# IRTxRx.net
KiCad netlist of a schematic drawn in Altium Designer
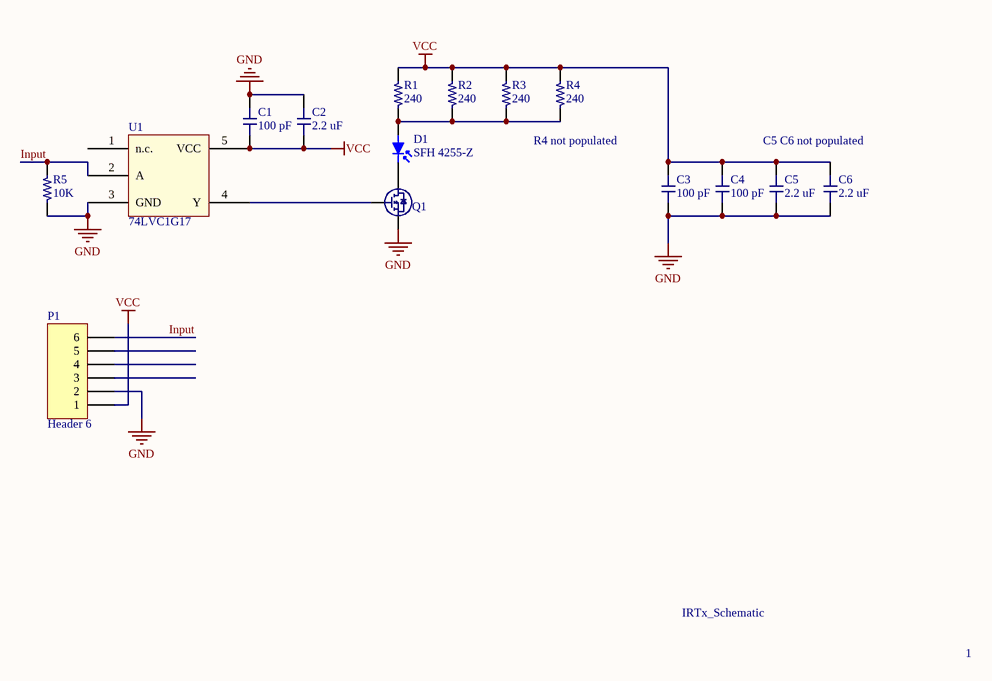
[diagram p0: IRTxRx.SchDoc]

(export (version "E")
  (design (tool "Eeschema 10.0.6"))
  (components
    (comp (ref "C1")
      (value "100 pF")
      (footprint "C_0603")
      (description "CAP CER 100PF 50V C0G/NP0 0603")
      (fields (field (name "Comment") "06035A101JAT2A"))
      (libsource (lib "Capacitor") (part "06035A101JAT2A"))
    )
    (comp (ref "C2")
      (value "2.2 uF")
      (footprint "C_0603")
      (description "Vishay VJ Series")
      (fields (field (name "Comment") "C1608X7R1A225K080AC"))
      (libsource (lib "Capacitor") (part "CAP CER 2.2UF 10V 10% X7R 0603"))
    )
    (comp (ref "C3")
      (value "100 pF")
      (footprint "C_0603")
      (description "CAP CER 100PF 50V C0G/NP0 0603")
      (fields (field (name "Comment") "06035A101JAT2A"))
      (libsource (lib "Capacitor") (part "06035A101JAT2A"))
    )
    (comp (ref "C4")
      (value "100 pF")
      (footprint "C_0603")
      (description "CAP CER 100PF 50V C0G/NP0 0603")
      (fields (field (name "Comment") "06035A101JAT2A"))
      (libsource (lib "Capacitor") (part "06035A101JAT2A"))
    )
    (comp (ref "C5")
      (value "2.2 uF")
      (footprint "C_0603")
      (description "Vishay VJ Series")
      (fields (field (name "Comment") "C1608X7R1A225K080AC"))
      (libsource (lib "Capacitor") (part "CAP CER 2.2UF 10V 10% X7R 0603"))
    )
    (comp (ref "C6")
      (value "2.2 uF")
      (footprint "C_0603")
      (description "Vishay VJ Series")
      (fields (field (name "Comment") "C1608X7R1A225K080AC"))
      (libsource (lib "Capacitor") (part "CAP CER 2.2UF 10V 10% X7R 0603"))
    )
    (comp (ref "D1")
      (value "SFH 4255-Z")
      (footprint "SFH4255")
      (description "EMITTER IR 860NM 100MA SMD")
      (libsource (lib "Diode") (part "SFH 4255-Z"))
    )
    (comp (ref "P1")
      (value "Header 6")
      (footprint "HDR1X6")
      (description "Header, 6-Pin")
      (fields (field (name "PUBLISHER") "Altium Limited"))
      (libsource (lib "Miscellaneous Connectors") (part "Header 6"))
    )
    (comp (ref "Q1")
      (value "ZXMN2A01FTA")
      (footprint "SOT23")
      (description "MOSFET N-CH 20V 1.9A SOT23-3")
      (libsource (lib "Discrete") (part "ZXMN2A01FTA"))
    )
    (comp (ref "R1")
      (value "240")
      (footprint "R_0603")
      (description "Panasonic ERJ-3EK")
      (fields (field (name "Comment") "RES 240 OHM 1/10W 1% 0603 SMD"))
      (libsource (lib "Resistor") (part "RES 240 OHM 1/10W 1% 0603 SMD"))
    )
    (comp (ref "R2")
      (value "240")
      (footprint "R_0603")
      (description "Panasonic ERJ-3EK")
      (fields (field (name "Comment") "RES 240 OHM 1/10W 1% 0603 SMD"))
      (libsource (lib "Resistor") (part "RES 240 OHM 1/10W 1% 0603 SMD"))
    )
    (comp (ref "R3")
      (value "240")
      (footprint "R_0603")
      (description "Panasonic ERJ-3EK")
      (fields (field (name "Comment") "RES 240 OHM 1/10W 1% 0603 SMD"))
      (libsource (lib "Resistor") (part "RES 240 OHM 1/10W 1% 0603 SMD"))
    )
    (comp (ref "R4")
      (value "240")
      (footprint "R_0603")
      (description "Panasonic ERJ-3EK")
      (fields (field (name "Comment") "RES 240 OHM 1/10W 1% 0603 SMD"))
      (libsource (lib "Resistor") (part "RES 240 OHM 1/10W 1% 0603 SMD"))
    )
    (comp (ref "R5")
      (value "10K")
      (footprint "R_0603")
      (description "Panasonic ERJ-3EK")
      (fields (field (name "Comment") "RES 10K OHM 1/10W 1% 0603 SMD"))
      (libsource (lib "Resistor") (part "RES 10K OHM 1/10W 1% 0603 SMD"))
    )
    (comp (ref "U1")
      (value "74LVC1G17")
      (footprint "SOT_353")
      (description "IC BUF NON-INVERT 5.5V 5TSSOP")
      (libsource (lib "Discrete") (part "74LVC1G17"))
    )
  )
  (nets
    (net (code "1") (name "/Input") (class "Default")
      (node (ref "P1") (pin "6") (pinfunction "6_6") (pintype "passive"))
      (node (ref "R5") (pin "1") (pinfunction "1_1") (pintype "passive"))
      (node (ref "U1") (pin "2") (pinfunction "A_2") (pintype "passive"))
    )
    (net (code "2") (name "GND") (class "Default")
      (node (ref "C1") (pin "2") (pinfunction "2_2") (pintype "passive"))
      (node (ref "C2") (pin "2") (pinfunction "2_2") (pintype "passive"))
      (node (ref "C3") (pin "2") (pinfunction "2_2") (pintype "passive"))
      (node (ref "C4") (pin "2") (pinfunction "2_2") (pintype "passive"))
      (node (ref "C5") (pin "2") (pinfunction "2_2") (pintype "passive"))
      (node (ref "C6") (pin "2") (pinfunction "2_2") (pintype "passive"))
      (node (ref "P1") (pin "2") (pinfunction "2_2") (pintype "passive"))
      (node (ref "Q1") (pin "2") (pinfunction "S_2") (pintype "passive"))
      (node (ref "R5") (pin "2") (pinfunction "2_2") (pintype "passive"))
      (node (ref "U1") (pin "3") (pinfunction "GND_3") (pintype "passive"))
    )
    (net (code "3") (name "Net-(D1-anode)") (class "Default")
      (node (ref "D1") (pin "1") (pinfunction "anode_1") (pintype "passive"))
      (node (ref "R1") (pin "2") (pinfunction "2_2") (pintype "passive"))
      (node (ref "R2") (pin "2") (pinfunction "2_2") (pintype "passive"))
      (node (ref "R3") (pin "2") (pinfunction "2_2") (pintype "passive"))
      (node (ref "R4") (pin "2") (pinfunction "2_2") (pintype "passive"))
    )
    (net (code "4") (name "Net-(D1-cathode)") (class "Default")
      (node (ref "D1") (pin "2") (pinfunction "cathode_2") (pintype "passive"))
      (node (ref "Q1") (pin "3") (pinfunction "D_3") (pintype "passive"))
    )
    (net (code "5") (name "Net-(Q1-G)") (class "Default")
      (node (ref "Q1") (pin "1") (pinfunction "G_1") (pintype "passive"))
      (node (ref "U1") (pin "4") (pinfunction "Y_4") (pintype "passive"))
    )
    (net (code "6") (name "VCC") (class "Default")
      (node (ref "C1") (pin "1") (pinfunction "1_1") (pintype "passive"))
      (node (ref "C2") (pin "1") (pinfunction "1_1") (pintype "passive"))
      (node (ref "C3") (pin "1") (pinfunction "1_1") (pintype "passive"))
      (node (ref "C4") (pin "1") (pinfunction "1_1") (pintype "passive"))
      (node (ref "C5") (pin "1") (pinfunction "1_1") (pintype "passive"))
      (node (ref "C6") (pin "1") (pinfunction "1_1") (pintype "passive"))
      (node (ref "P1") (pin "1") (pinfunction "1_1") (pintype "passive"))
      (node (ref "R1") (pin "1") (pinfunction "1_1") (pintype "passive"))
      (node (ref "R2") (pin "1") (pinfunction "1_1") (pintype "passive"))
      (node (ref "R3") (pin "1") (pinfunction "1_1") (pintype "passive"))
      (node (ref "R4") (pin "1") (pinfunction "1_1") (pintype "passive"))
      (node (ref "U1") (pin "5") (pinfunction "VCC_5") (pintype "passive"))
    )
    (net (code "7") (name "unconnected-(P1-Pad3)") (class "Default")
      (node (ref "P1") (pin "3") (pinfunction "3_3") (pintype "passive"))
    )
    (net (code "8") (name "unconnected-(P1-Pad4)") (class "Default")
      (node (ref "P1") (pin "4") (pinfunction "4_4") (pintype "passive"))
    )
    (net (code "9") (name "unconnected-(P1-Pad5)") (class "Default")
      (node (ref "P1") (pin "5") (pinfunction "5_5") (pintype "passive"))
    )
    (net (code "10") (name "unconnected-(U1-n.c.-Pad1)") (class "Default")
      (node (ref "U1") (pin "1") (pinfunction "n.c._1") (pintype "passive"))
    )
  )
)
